# Ikea_Environmental_Sensors.net
KiCad netlist of a schematic drawn in Altium Designer
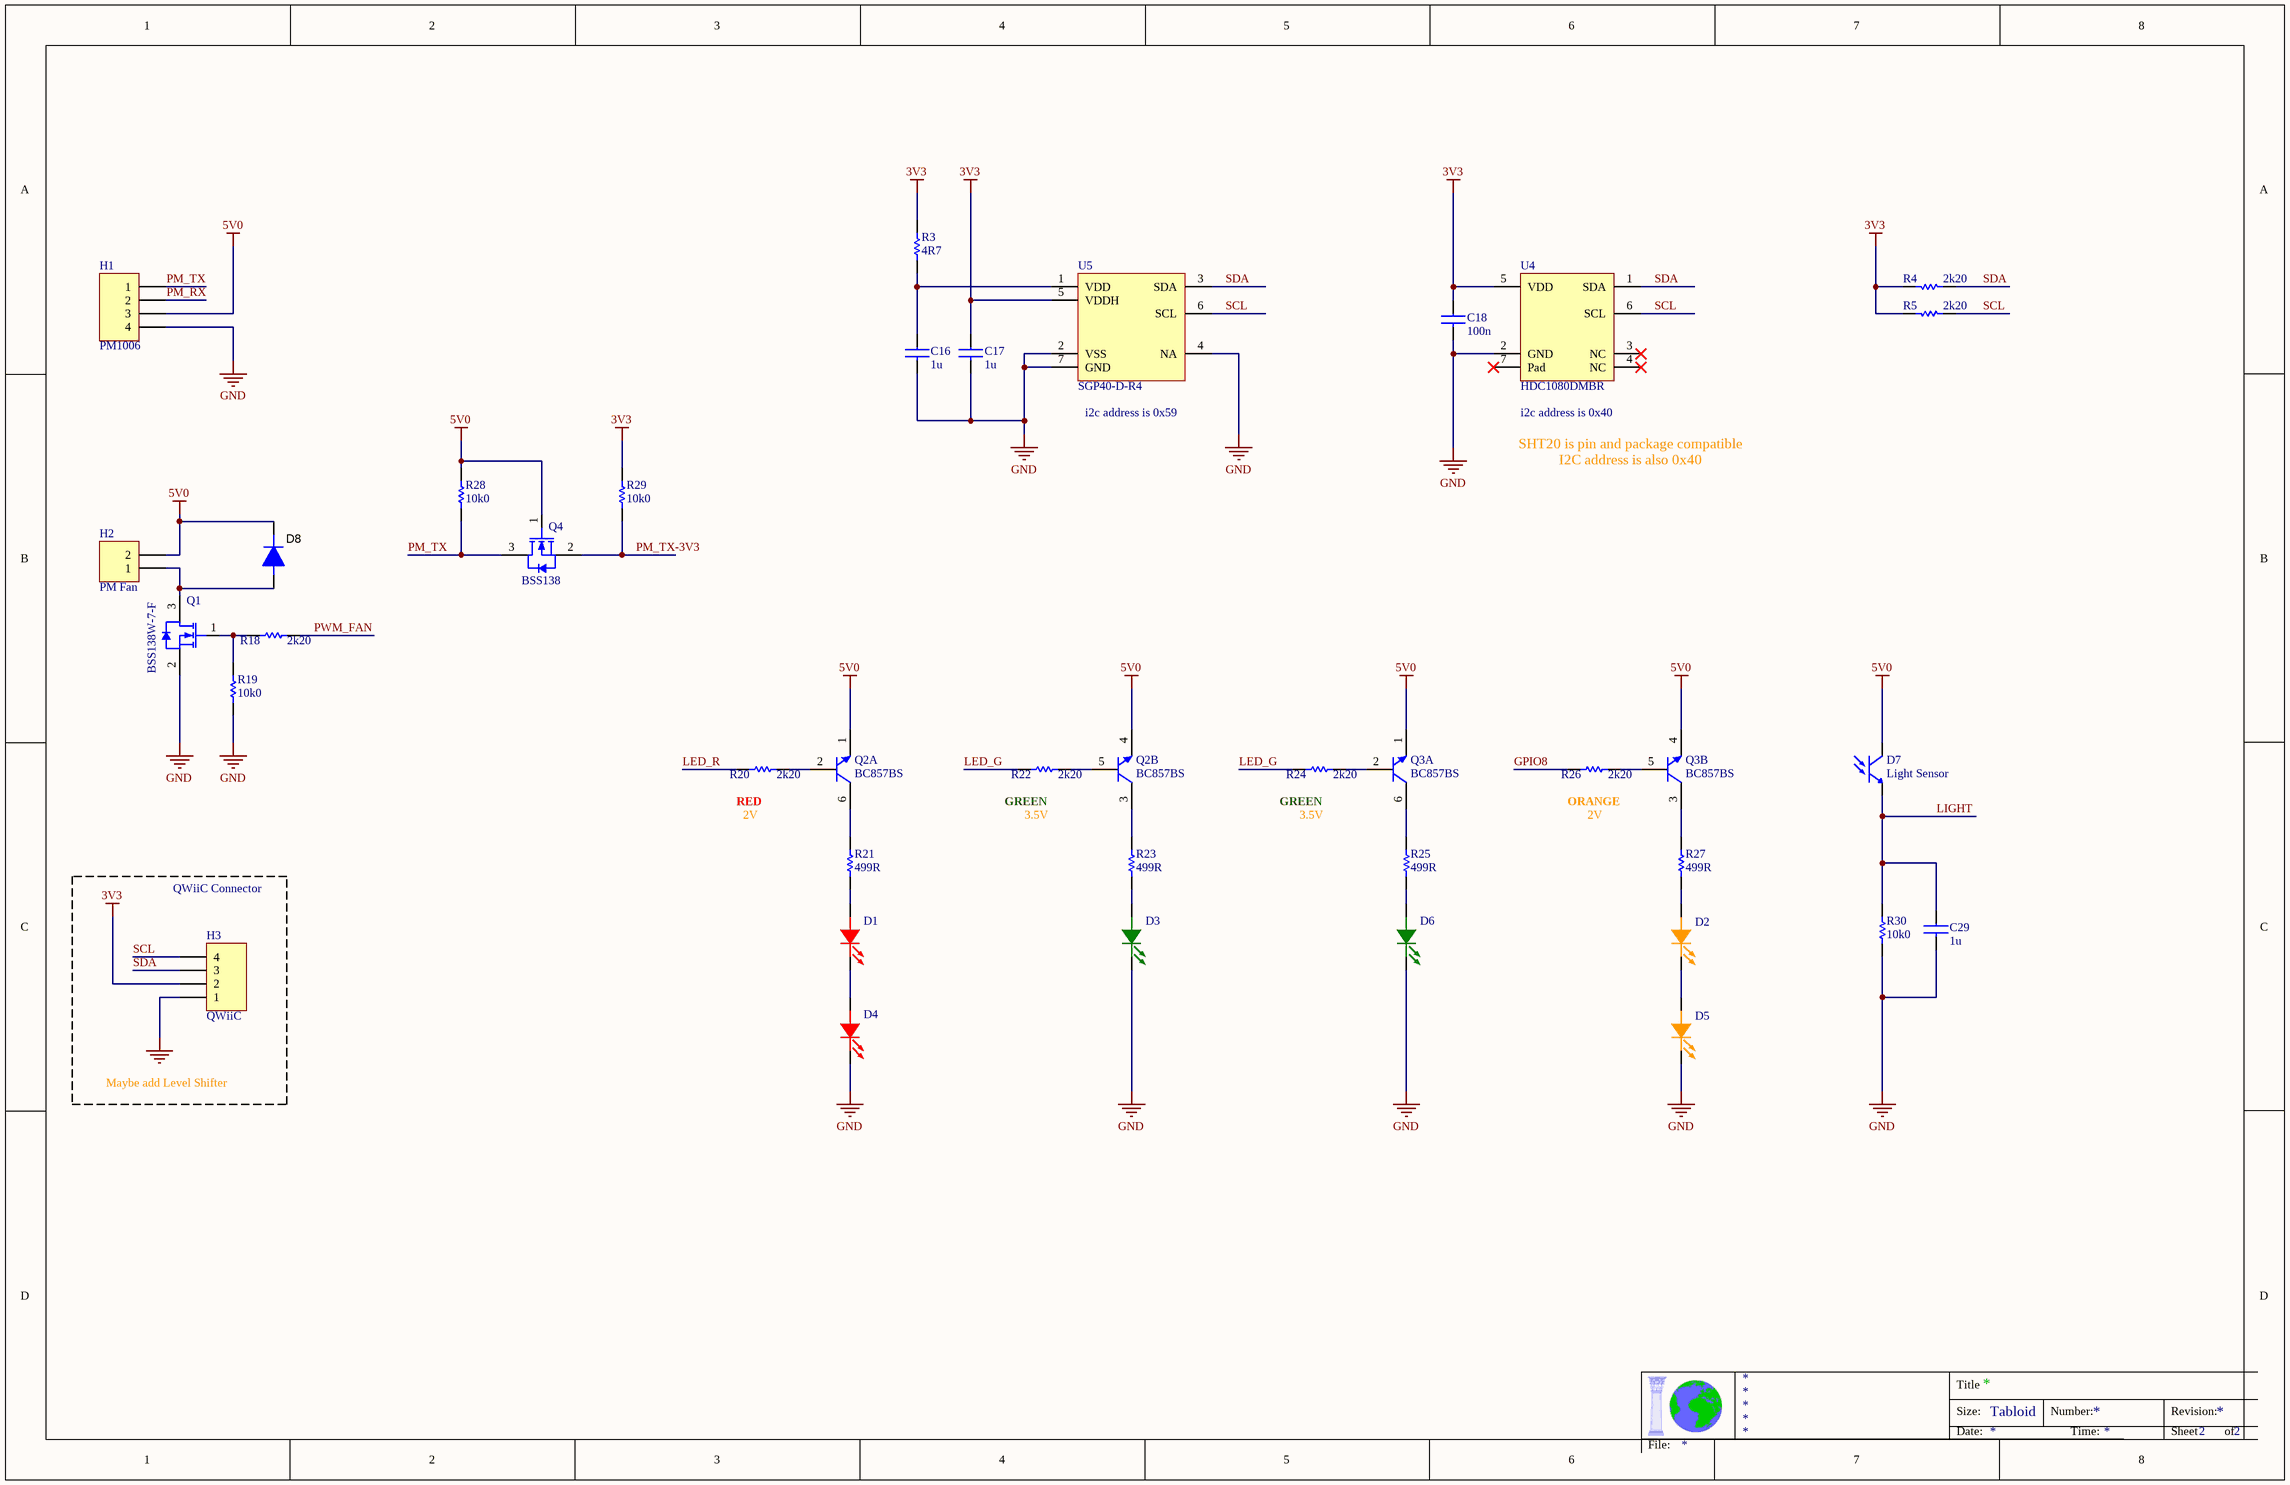
[diagram p0: Ikea Environmental Sensors.SchDoc]

(export (version "E")
  (design (tool "Eeschema 10.0.6"))
  (components
    (comp (ref "C16")
      (value "1u")
      (footprint "C_0402_N")
      (description "Cap, Chip, 1uF, 10V, 10%, X5R, 0402")
      (fields (field (name "MANUFACTURER") "NIC"))
      (libsource (lib "GLIB") (part "C_1u_10V_10_0402_NIC"))
    )
    (comp (ref "C17")
      (value "1u")
      (footprint "C_0402_N")
      (description "Cap, Chip, 1uF, 10V, 10%, X5R, 0402")
      (fields (field (name "MANUFACTURER") "NIC"))
      (libsource (lib "GLIB") (part "C_1u_10V_10_0402_NIC"))
    )
    (comp (ref "C18")
      (value "100n")
      (footprint "C_0402_N")
      (description "Cap, Chip, 100nF, 16V, +/-10%, X7R, 0402")
      (fields (field (name "MANUFACTURER") "NIC"))
      (libsource (lib "GLIB") (part "C_100n_16V_10_0402_NIC"))
    )
    (comp (ref "C29")
      (value "1u")
      (footprint "C_0402_N")
      (description "Cap, Chip, 1uF, 10V, 10%, X5R, 0402")
      (fields (field (name "MANUFACTURER") "NIC"))
      (libsource (lib "GLIB") (part "C_1u_10V_10_0402_NIC"))
    )
    (comp (ref "D1")
      (value "0603 Red")
      (footprint "D_0603")
      (description "0603 LED, Red, Vf=1.6-2.4V")
      (fields (field (name "MANUFACTURER") "Lite-on") (field (name "JLCPCB PART #") "C84256"))
      (libsource (lib "GLIB") (part "D_LED-0603_LTST-C190KRKT"))
    )
    (comp (ref "D2")
      (value "0603 Orange")
      (footprint "D_0603")
      (description "0603 LED, Orange, Vf=2.0-2.4V")
      (fields (field (name "MANUFACTURER") "Lite-on") (field (name "JLCPCB PART #") "C146215"))
      (libsource (lib "GLIB") (part "D_LED-0603_LTST-C190KFKT"))
    )
    (comp (ref "D3")
      (value "0603 Green")
      (footprint "D_0603")
      (description "0603 LED, Green, Vf=1.9-2.4V")
      (fields (field (name "MANUFACTURER") "Lite-on") (field (name "JLCPCB PART #") "C72043"))
      (libsource (lib "GLIB") (part "D_LED-0603_LTST-C190KGKT"))
    )
    (comp (ref "D4")
      (value "0603 Red")
      (footprint "D_0603")
      (description "0603 LED, Red, Vf=1.6-2.4V")
      (fields (field (name "MANUFACTURER") "Lite-on") (field (name "JLCPCB PART #") "C84256"))
      (libsource (lib "GLIB") (part "D_LED-0603_LTST-C190KRKT"))
    )
    (comp (ref "D5")
      (value "0603 Orange")
      (footprint "D_0603")
      (description "0603 LED, Orange, Vf=2.0-2.4V")
      (fields (field (name "MANUFACTURER") "Lite-on") (field (name "JLCPCB PART #") "C146215"))
      (libsource (lib "GLIB") (part "D_LED-0603_LTST-C190KFKT"))
    )
    (comp (ref "D6")
      (value "0603 Green")
      (footprint "D_0603")
      (description "0603 LED, Green, Vf=1.9-2.4V")
      (fields (field (name "MANUFACTURER") "Lite-on") (field (name "JLCPCB PART #") "C72043"))
      (libsource (lib "GLIB") (part "D_LED-0603_LTST-C190KGKT"))
    )
    (comp (ref "D7")
      (value "Light Sensor")
      (footprint "XDCR_ALS-PT19-315C/L177/TR8")
      (description "Sensor, Photo, 630NM, 2-SMD")
      (fields (field (name "MANUFACTURER") "Lite-on") (field (name "JLCPCB PART #") "C146233"))
      (libsource (lib "GLIB") (part "Q_Photodiode_ALS-PT19_2-SMD"))
    )
    (comp (ref "D8")
      (value "1N4148")
      (footprint "SOD-523")
      (description "Diode, Signal, 300-mA, 75-V, 350-mW, SOD523")
      (fields (field (name "MANUFACTURER") "NextGeb") (field (name "JLCPCB PART #") "C511874"))
      (libsource (lib "GLIB") (part "D_1N4148WT_SOD523"))
    )
    (comp (ref "H1")
      (value "PM1006")
      (footprint "HDR1x4_1.5mm_RA_TH")
      (description "Header, 4-Pin")
      (fields (field (name "MANUFACTURER") "JST") (field (name "JLCPCB PART #") "C225169"))
      (libsource (lib "GLIB") (part "Header 4_RA_1.5mm_TH"))
    )
    (comp (ref "H2")
      (value "PM Fan")
      (footprint "HDR1x2_1.25mm_RA_TH")
      (description "Header, 2-Pin")
      (libsource (lib "GLIB") (part "Header 2_1.25_TH"))
    )
    (comp (ref "H3")
      (value "QWiiC")
      (footprint "JST SM04B-SRSS-TB")
      (description "Header, 4-Pin")
      (fields (field (name "MANUFACTURER") "JST") (field (name "JLCPCB PART #") "C145956"))
      (libsource (lib "GLIB") (part "Header 4_RA_1.00mm_SMT"))
    )
    (comp (ref "Q1")
      (value "BSS138W-7-F")
      (footprint "SOT323")
      (description "MOSFET N-Channel 50V, 200mA, 200mW, SOT323")
      (fields (field (name "MANUFACTURER") "Diodes Inc."))
      (libsource (lib "GLIB") (part "Q_N-CH_50V_A200_BSS138W_SOT323"))
    )
    (comp (ref "Q2")
      (value "BC857BS")
      (footprint "SOT363_N")
      (description "PNP GP Double Transistor, 45V,100mA, SOT363")
      (fields (field (name "MANUFACTURER") "NXP") (field (name "JLCPCB PART #") "C8654"))
      (libsource (lib "GLIB") (part "Q_BC857BS,115_SOT363"))
    )
    (comp (ref "Q3")
      (value "BC857BS")
      (footprint "SOT363_N")
      (description "PNP GP Double Transistor, 45V,100mA, SOT363")
      (fields (field (name "MANUFACTURER") "NXP") (field (name "JLCPCB PART #") "C8654"))
      (libsource (lib "GLIB") (part "Q_BC857BS,115_SOT363"))
    )
    (comp (ref "Q4")
      (value "BSS138")
      (footprint "SOT323")
      (description "MOSFET N-Channel 50V, 200mA, 200mW, SOT323")
      (fields (field (name "MANUFACTURER") "Diodes Inc."))
      (libsource (lib "GLIB") (part "Q_N-CH_50V_A200_BSS138W_SOT323"))
    )
    (comp (ref "R3")
      (value "4R7")
      (footprint "R_0402-N")
      (description "Resistor, 4.7 Ω, 1%, 0.06W, 0402")
      (fields (field (name "MANUFACTURER") "NIC"))
      (libsource (lib "GLIB") (part "R_4R7_60mW_1_0402_NIC"))
    )
    (comp (ref "R4")
      (value "2k20")
      (footprint "R_0402-N")
      (description "Resistor, 2.20 kΩ, 1%, 0.06W, 0402")
      (fields (field (name "MANUFACTURER") "NIC"))
      (libsource (lib "GLIB") (part "R_2k20_60mW_1_0402_NIC"))
    )
    (comp (ref "R5")
      (value "2k20")
      (footprint "R_0402-N")
      (description "Resistor, 2.20 kΩ, 1%, 0.06W, 0402")
      (fields (field (name "MANUFACTURER") "NIC"))
      (libsource (lib "GLIB") (part "R_2k20_60mW_1_0402_NIC"))
    )
    (comp (ref "R18")
      (value "2k20")
      (footprint "R_0402-N")
      (description "Resistor, 2.20 kΩ, 1%, 0.06W, 0402")
      (fields (field (name "MANUFACTURER") "NIC"))
      (libsource (lib "GLIB") (part "R_2k20_60mW_1_0402_NIC"))
    )
    (comp (ref "R19")
      (value "10k0")
      (footprint "R_0402-N")
      (description "Resistor, 10.0 kΩ, 1%, 0.06W, 0402")
      (fields (field (name "MANUFACTURER") "NIC"))
      (libsource (lib "GLIB") (part "R_10k0_60mW_1_0402_NIC"))
    )
    (comp (ref "R20")
      (value "2k20")
      (footprint "R_0402-N")
      (description "Resistor, 2.20 kΩ, 1%, 0.06W, 0402")
      (fields (field (name "MANUFACTURER") "NIC"))
      (libsource (lib "GLIB") (part "R_2k20_60mW_1_0402_NIC"))
    )
    (comp (ref "R21")
      (value "499R")
      (footprint "R_0402-N")
      (description "Resistor, 499 Ω, 1%, 0.06W, 0402")
      (fields (field (name "MANUFACTURER") "NIC"))
      (libsource (lib "GLIB") (part "R_499R_60mW_1_0402_NIC"))
    )
    (comp (ref "R22")
      (value "2k20")
      (footprint "R_0402-N")
      (description "Resistor, 2.20 kΩ, 1%, 0.06W, 0402")
      (fields (field (name "MANUFACTURER") "NIC"))
      (libsource (lib "GLIB") (part "R_2k20_60mW_1_0402_NIC"))
    )
    (comp (ref "R23")
      (value "499R")
      (footprint "R_0402-N")
      (description "Resistor, 499 Ω, 1%, 0.06W, 0402")
      (fields (field (name "MANUFACTURER") "NIC"))
      (libsource (lib "GLIB") (part "R_499R_60mW_1_0402_NIC"))
    )
    (comp (ref "R24")
      (value "2k20")
      (footprint "R_0402-N")
      (description "Resistor, 2.20 kΩ, 1%, 0.06W, 0402")
      (fields (field (name "MANUFACTURER") "NIC"))
      (libsource (lib "GLIB") (part "R_2k20_60mW_1_0402_NIC"))
    )
    (comp (ref "R25")
      (value "499R")
      (footprint "R_0402-N")
      (description "Resistor, 499 Ω, 1%, 0.06W, 0402")
      (fields (field (name "MANUFACTURER") "NIC"))
      (libsource (lib "GLIB") (part "R_499R_60mW_1_0402_NIC"))
    )
    (comp (ref "R26")
      (value "2k20")
      (footprint "R_0402-N")
      (description "Resistor, 2.20 kΩ, 1%, 0.06W, 0402")
      (fields (field (name "MANUFACTURER") "NIC"))
      (libsource (lib "GLIB") (part "R_2k20_60mW_1_0402_NIC"))
    )
    (comp (ref "R27")
      (value "499R")
      (footprint "R_0402-N")
      (description "Resistor, 499 Ω, 1%, 0.06W, 0402")
      (fields (field (name "MANUFACTURER") "NIC"))
      (libsource (lib "GLIB") (part "R_499R_60mW_1_0402_NIC"))
    )
    (comp (ref "R28")
      (value "10k0")
      (footprint "R_0402-N")
      (description "Resistor, 10.0 kΩ, 1%, 0.06W, 0402")
      (fields (field (name "MANUFACTURER") "NIC"))
      (libsource (lib "GLIB") (part "R_10k0_60mW_1_0402_NIC"))
    )
    (comp (ref "R29")
      (value "10k0")
      (footprint "R_0402-N")
      (description "Resistor, 10.0 kΩ, 1%, 0.06W, 0402")
      (fields (field (name "MANUFACTURER") "NIC"))
      (libsource (lib "GLIB") (part "R_10k0_60mW_1_0402_NIC"))
    )
    (comp (ref "R30")
      (value "10k0")
      (footprint "R_0402-N")
      (description "Resistor, 10.0 kΩ, 1%, 0.06W, 0402")
      (fields (field (name "MANUFACTURER") "NIC"))
      (libsource (lib "GLIB") (part "R_10k0_60mW_1_0402_NIC"))
    )
    (comp (ref "U4")
      (value "HDC1080DMBR")
      (footprint "DMB0006A")
      (description "IC, Digital Temp & Humidity Sensor, DFN6")
      (fields (field (name "MANUFACTURER") "Texas Instruments") (field (name "JLCPCB PART #") "C82227"))
      (libsource (lib "GLIB") (part "U_HDC1080DMBR_DFN6"))
    )
    (comp (ref "U5")
      (value "SGP40-D-R4")
      (footprint "SGP40_SEN-M")
      (description "IC, Air Quality Gas Sensor, DFN6")
      (fields (field (name "MANUFACTURER") "Sensirion"))
      (libsource (lib "GLIB") (part "U_SGP40-D-R4_DFN6"))
    )
  )
  (nets
    (net (code "1") (name "/GPIO8") (class "Default")
      (node (ref "R26") (pin "2") (pinfunction "2_2") (pintype "passive"))
    )
    (net (code "2") (name "/LED_G") (class "Default")
      (node (ref "R22") (pin "2") (pinfunction "2_2") (pintype "passive"))
      (node (ref "R24") (pin "2") (pinfunction "2_2") (pintype "passive"))
    )
    (net (code "3") (name "/LED_R") (class "Default")
      (node (ref "R20") (pin "2") (pinfunction "2_2") (pintype "passive"))
    )
    (net (code "4") (name "/LIGHT") (class "Default")
      (node (ref "C29") (pin "1") (pinfunction "1_1") (pintype "passive"))
      (node (ref "D7") (pin "2") (pinfunction "CATHODE_2") (pintype "passive"))
      (node (ref "R30") (pin "2") (pinfunction "2_2") (pintype "passive"))
    )
    (net (code "5") (name "/PM_RX") (class "Default")
      (node (ref "H1") (pin "2") (pinfunction "2_2") (pintype "passive"))
    )
    (net (code "6") (name "/PM_TX") (class "Default")
      (node (ref "H1") (pin "1") (pinfunction "1_1") (pintype "passive"))
      (node (ref "Q4") (pin "3") (pinfunction "D_3") (pintype "passive"))
      (node (ref "R28") (pin "1") (pinfunction "1_1") (pintype "passive"))
    )
    (net (code "7") (name "/PM_TX-3V3") (class "Default")
      (node (ref "Q4") (pin "2") (pinfunction "S_2") (pintype "passive"))
      (node (ref "R29") (pin "1") (pinfunction "1_1") (pintype "passive"))
    )
    (net (code "8") (name "/PWM_FAN") (class "Default")
      (node (ref "R18") (pin "1") (pinfunction "1_1") (pintype "passive"))
    )
    (net (code "9") (name "/SCL") (class "Default")
      (node (ref "H3") (pin "4") (pinfunction "4_4") (pintype "passive"))
      (node (ref "R5") (pin "2") (pinfunction "2_2") (pintype "passive"))
      (node (ref "U4") (pin "6") (pinfunction "SCL_6") (pintype "passive"))
      (node (ref "U5") (pin "6") (pinfunction "SCL_6") (pintype "passive"))
    )
    (net (code "10") (name "/SDA") (class "Default")
      (node (ref "H3") (pin "3") (pinfunction "3_3") (pintype "passive"))
      (node (ref "R4") (pin "2") (pinfunction "2_2") (pintype "passive"))
      (node (ref "U4") (pin "1") (pinfunction "SDA_1") (pintype "passive"))
      (node (ref "U5") (pin "3") (pinfunction "SDA_3") (pintype "passive"))
    )
    (net (code "11") (name "3V3") (class "Default")
      (node (ref "C17") (pin "1") (pinfunction "1_1") (pintype "passive"))
      (node (ref "C18") (pin "1") (pinfunction "1_1") (pintype "passive"))
      (node (ref "H3") (pin "2") (pinfunction "2_2") (pintype "passive"))
      (node (ref "R29") (pin "2") (pinfunction "2_2") (pintype "passive"))
      (node (ref "R3") (pin "2") (pinfunction "2_2") (pintype "passive"))
      (node (ref "R4") (pin "1") (pinfunction "1_1") (pintype "passive"))
      (node (ref "R5") (pin "1") (pinfunction "1_1") (pintype "passive"))
      (node (ref "U4") (pin "5") (pinfunction "VDD_5") (pintype "power_in"))
      (node (ref "U5") (pin "5") (pinfunction "VDDH_5") (pintype "power_in"))
    )
    (net (code "12") (name "5V0") (class "Default")
      (node (ref "D7") (pin "1") (pinfunction "ANODE_1") (pintype "passive"))
      (node (ref "D8") (pin "2") (pinfunction "K_2") (pintype "passive"))
      (node (ref "H1") (pin "3") (pinfunction "3_3") (pintype "passive"))
      (node (ref "H2") (pin "2") (pinfunction "2_2") (pintype "passive"))
      (node (ref "Q2") (pin "1") (pinfunction "E_1") (pintype "passive"))
      (node (ref "Q2") (pin "4") (pinfunction "E_4") (pintype "passive"))
      (node (ref "Q3") (pin "1") (pinfunction "E_1") (pintype "passive"))
      (node (ref "Q3") (pin "4") (pinfunction "E_4") (pintype "passive"))
      (node (ref "Q4") (pin "1") (pinfunction "G_1") (pintype "passive"))
      (node (ref "R28") (pin "2") (pinfunction "2_2") (pintype "passive"))
    )
    (net (code "13") (name "GND") (class "Default")
      (node (ref "C16") (pin "2") (pinfunction "2_2") (pintype "passive"))
      (node (ref "C17") (pin "2") (pinfunction "2_2") (pintype "passive"))
      (node (ref "C18") (pin "2") (pinfunction "2_2") (pintype "passive"))
      (node (ref "C29") (pin "2") (pinfunction "2_2") (pintype "passive"))
      (node (ref "D3") (pin "2") (pinfunction "CATHODE_2") (pintype "passive"))
      (node (ref "D4") (pin "2") (pinfunction "CATHODE_2") (pintype "passive"))
      (node (ref "D5") (pin "2") (pinfunction "CATHODE_2") (pintype "passive"))
      (node (ref "D6") (pin "2") (pinfunction "CATHODE_2") (pintype "passive"))
      (node (ref "H1") (pin "4") (pinfunction "4_4") (pintype "passive"))
      (node (ref "H3") (pin "1") (pinfunction "1_1") (pintype "passive"))
      (node (ref "Q1") (pin "2") (pinfunction "S_2") (pintype "passive"))
      (node (ref "R19") (pin "1") (pinfunction "1_1") (pintype "passive"))
      (node (ref "R30") (pin "1") (pinfunction "1_1") (pintype "passive"))
      (node (ref "U4") (pin "2") (pinfunction "GND_2") (pintype "power_in"))
      (node (ref "U5") (pin "2") (pinfunction "VSS_2") (pintype "passive"))
      (node (ref "U5") (pin "4") (pinfunction "NA_4") (pintype "passive"))
      (node (ref "U5") (pin "7") (pinfunction "GND_7") (pintype "passive"))
    )
    (net (code "14") (name "Net-(D1-ANODE)") (class "Default")
      (node (ref "D1") (pin "1") (pinfunction "ANODE_1") (pintype "passive"))
      (node (ref "R21") (pin "1") (pinfunction "1_1") (pintype "passive"))
    )
    (net (code "15") (name "Net-(D1-CATHODE)") (class "Default")
      (node (ref "D1") (pin "2") (pinfunction "CATHODE_2") (pintype "passive"))
      (node (ref "D4") (pin "1") (pinfunction "ANODE_1") (pintype "passive"))
    )
    (net (code "16") (name "Net-(D2-ANODE)") (class "Default")
      (node (ref "D2") (pin "1") (pinfunction "ANODE_1") (pintype "passive"))
      (node (ref "R27") (pin "1") (pinfunction "1_1") (pintype "passive"))
    )
    (net (code "17") (name "Net-(D2-CATHODE)") (class "Default")
      (node (ref "D2") (pin "2") (pinfunction "CATHODE_2") (pintype "passive"))
      (node (ref "D5") (pin "1") (pinfunction "ANODE_1") (pintype "passive"))
    )
    (net (code "18") (name "Net-(D3-ANODE)") (class "Default")
      (node (ref "D3") (pin "1") (pinfunction "ANODE_1") (pintype "passive"))
      (node (ref "R23") (pin "1") (pinfunction "1_1") (pintype "passive"))
    )
    (net (code "19") (name "Net-(D6-ANODE)") (class "Default")
      (node (ref "D6") (pin "1") (pinfunction "ANODE_1") (pintype "passive"))
      (node (ref "R25") (pin "1") (pinfunction "1_1") (pintype "passive"))
    )
    (net (code "20") (name "Net-(D8-A)") (class "Default")
      (node (ref "D8") (pin "1") (pinfunction "A_1") (pintype "passive"))
      (node (ref "H2") (pin "1") (pinfunction "1_1") (pintype "passive"))
      (node (ref "Q1") (pin "3") (pinfunction "D_3") (pintype "passive"))
    )
    (net (code "21") (name "Net-(Q1-G)") (class "Default")
      (node (ref "Q1") (pin "1") (pinfunction "G_1") (pintype "passive"))
      (node (ref "R18") (pin "2") (pinfunction "2_2") (pintype "passive"))
      (node (ref "R19") (pin "2") (pinfunction "2_2") (pintype "passive"))
    )
    (net (code "22") (name "Net-(Q2A-B)") (class "Default")
      (node (ref "Q2") (pin "2") (pinfunction "B_2") (pintype "passive"))
      (node (ref "R20") (pin "1") (pinfunction "1_1") (pintype "passive"))
    )
    (net (code "23") (name "Net-(Q2A-C)") (class "Default")
      (node (ref "Q2") (pin "6") (pinfunction "C_6") (pintype "passive"))
      (node (ref "R21") (pin "2") (pinfunction "2_2") (pintype "passive"))
    )
    (net (code "24") (name "Net-(Q2B-B)") (class "Default")
      (node (ref "Q2") (pin "5") (pinfunction "B_5") (pintype "passive"))
      (node (ref "R22") (pin "1") (pinfunction "1_1") (pintype "passive"))
    )
    (net (code "25") (name "Net-(Q2B-C)") (class "Default")
      (node (ref "Q2") (pin "3") (pinfunction "C_3") (pintype "passive"))
      (node (ref "R23") (pin "2") (pinfunction "2_2") (pintype "passive"))
    )
    (net (code "26") (name "Net-(Q3A-B)") (class "Default")
      (node (ref "Q3") (pin "2") (pinfunction "B_2") (pintype "passive"))
      (node (ref "R24") (pin "1") (pinfunction "1_1") (pintype "passive"))
    )
    (net (code "27") (name "Net-(Q3A-C)") (class "Default")
      (node (ref "Q3") (pin "6") (pinfunction "C_6") (pintype "passive"))
      (node (ref "R25") (pin "2") (pinfunction "2_2") (pintype "passive"))
    )
    (net (code "28") (name "Net-(Q3B-B)") (class "Default")
      (node (ref "Q3") (pin "5") (pinfunction "B_5") (pintype "passive"))
      (node (ref "R26") (pin "1") (pinfunction "1_1") (pintype "passive"))
    )
    (net (code "29") (name "Net-(Q3B-C)") (class "Default")
      (node (ref "Q3") (pin "3") (pinfunction "C_3") (pintype "passive"))
      (node (ref "R27") (pin "2") (pinfunction "2_2") (pintype "passive"))
    )
    (net (code "30") (name "Net-(U5-VDD)") (class "Default")
      (node (ref "C16") (pin "1") (pinfunction "1_1") (pintype "passive"))
      (node (ref "R3") (pin "1") (pinfunction "1_1") (pintype "passive"))
      (node (ref "U5") (pin "1") (pinfunction "VDD_1") (pintype "power_in"))
    )
    (net (code "31") (name "unconnected-(U4-NC-Pad3)") (class "Default")
      (node (ref "U4") (pin "3") (pinfunction "NC_3") (pintype "passive+no_connect"))
    )
    (net (code "32") (name "unconnected-(U4-NC-Pad4)") (class "Default")
      (node (ref "U4") (pin "4") (pinfunction "NC_4") (pintype "passive+no_connect"))
    )
    (net (code "33") (name "unconnected-(U4-Pad-Pad7)") (class "Default")
      (node (ref "U4") (pin "7") (pinfunction "Pad_7") (pintype "power_in+no_connect"))
    )
  )
)
